# WS2811_Stepper.net
KiCad netlist of a schematic drawn in EAGLE
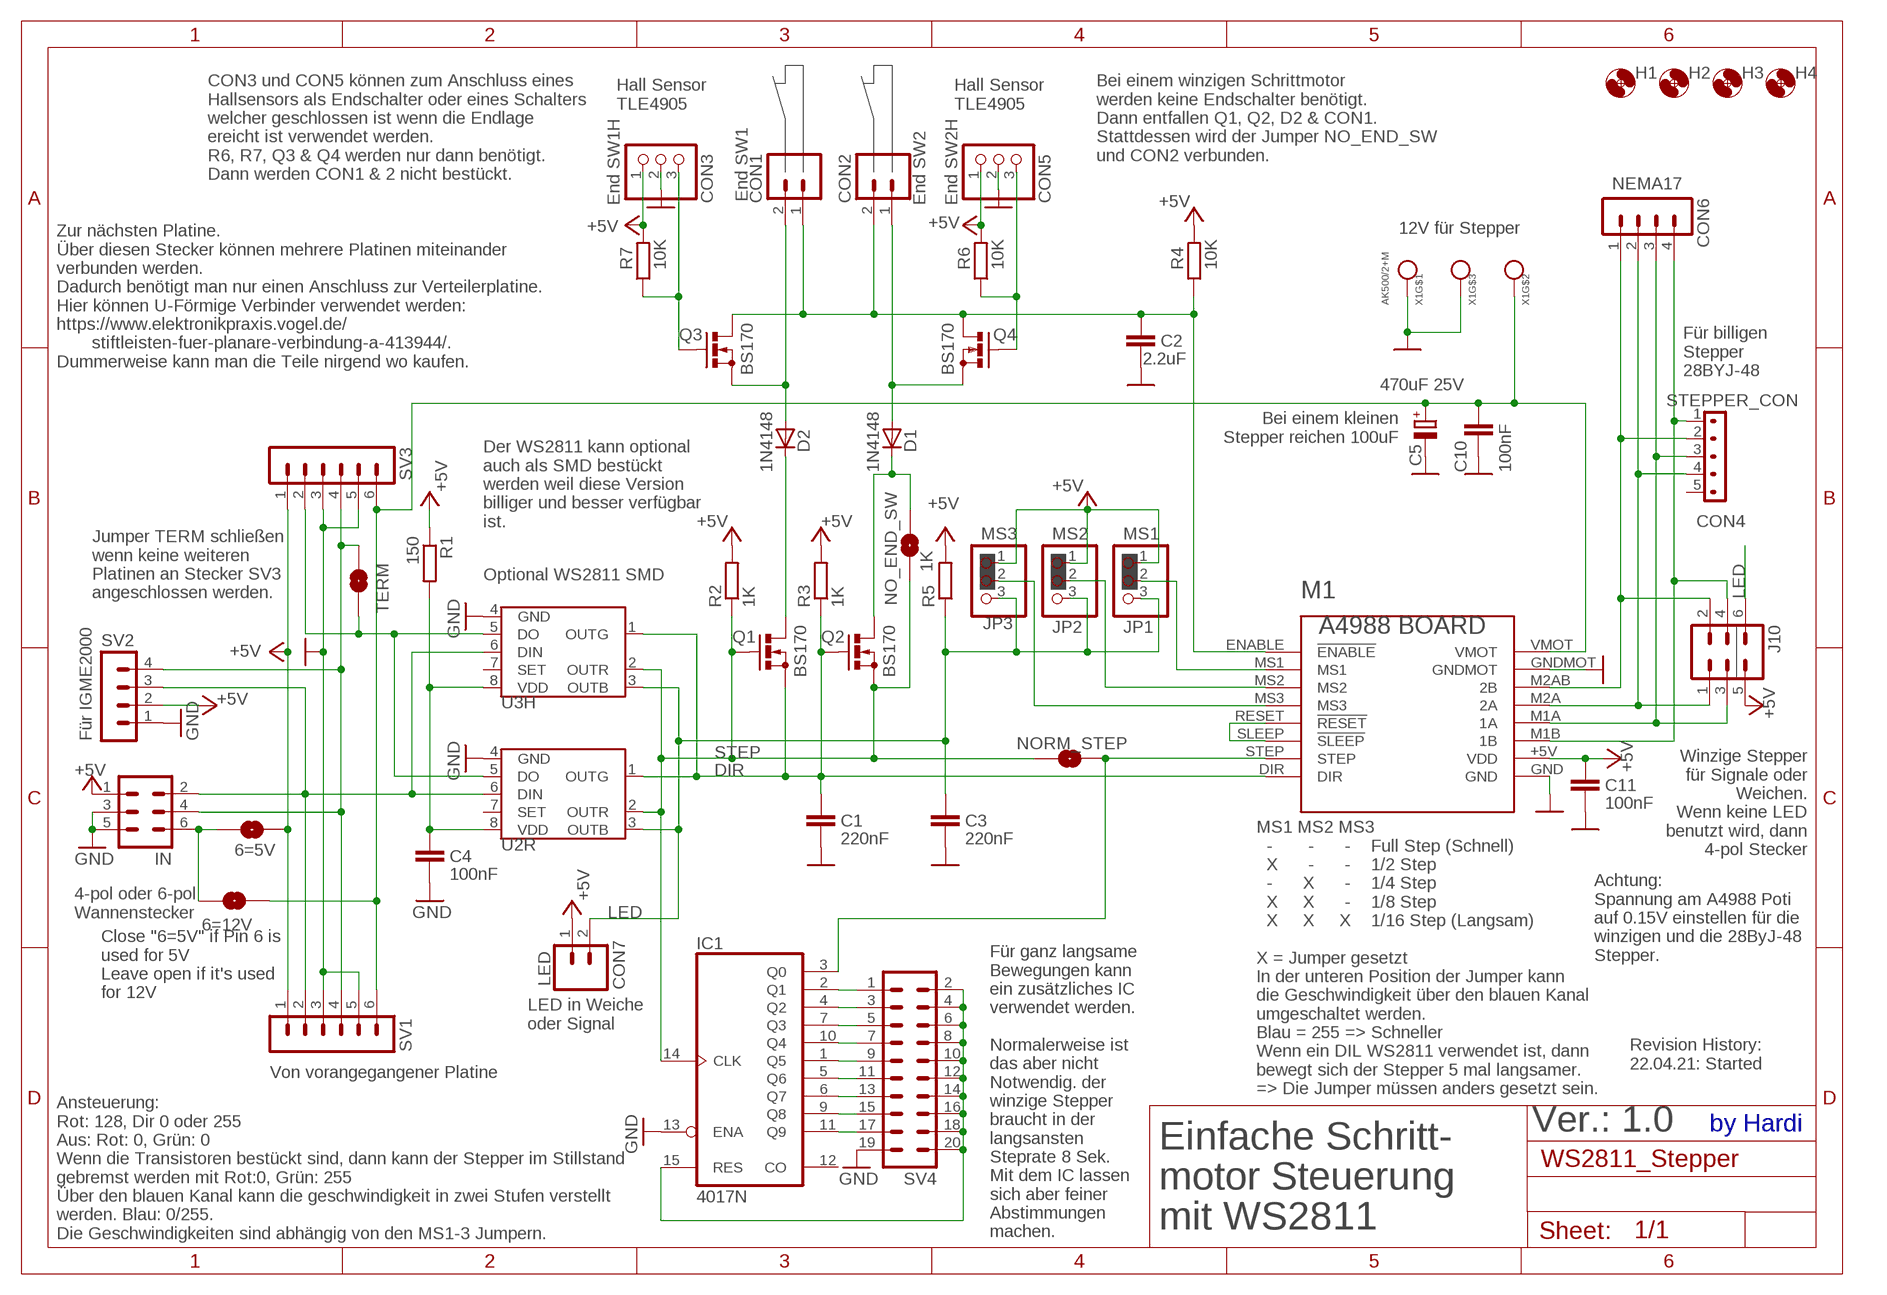
[diagram p0: schematic, sheet 1]

(export (version "E")
  (design (tool "Eeschema 10.0.6"))
  (components
    (comp (ref "6=5V")
      (value "SOLDERJUMPERNO")
      (footprint "eagle-import:SJ_2S-NO")
      (libsource (lib "eagle-import") (part "SOLDERJUMPERNO"))
    )
    (comp (ref "6=12V")
      (value "SOLDERJUMPERNO")
      (footprint "eagle-import:SJ_2S-NO")
      (libsource (lib "eagle-import") (part "SOLDERJUMPERNO"))
    )
    (comp (ref "C1")
      (value "220nF")
      (footprint "eagle-import:C050-024X044")
      (libsource (lib "eagle-import") (part "C-EU050-024X044"))
    )
    (comp (ref "C2")
      (value "2.2uF")
      (footprint "eagle-import:C050-024X044")
      (libsource (lib "eagle-import") (part "C-EU050-024X044"))
    )
    (comp (ref "C3")
      (value "220nF")
      (footprint "eagle-import:C050-024X044")
      (libsource (lib "eagle-import") (part "C-EU050-024X044"))
    )
    (comp (ref "C4")
      (value "100nF")
      (footprint "eagle-import:C050-024X044")
      (libsource (lib "eagle-import") (part "C-EU050-024X044"))
    )
    (comp (ref "C5")
      (value "470uF 25V")
      (footprint "eagle-import:E5-10,5")
      (libsource (lib "eagle-import") (part "CPOL-EUE5-10.5"))
    )
    (comp (ref "C10")
      (value "100nF")
      (footprint "eagle-import:C050-024X044")
      (libsource (lib "eagle-import") (part "C-EU050-024X044"))
    )
    (comp (ref "C11")
      (value "100nF")
      (footprint "eagle-import:C050-024X044")
      (libsource (lib "eagle-import") (part "C-EU050-024X044"))
    )
    (comp (ref "CON1")
      (value "End SW1")
      (footprint "eagle-import:1X02")
      (libsource (lib "eagle-import") (part "M02PTH"))
    )
    (comp (ref "CON2")
      (value "End SW2")
      (footprint "eagle-import:1X02")
      (libsource (lib "eagle-import") (part "M02PTH"))
    )
    (comp (ref "CON3")
      (value "End SW1H")
      (footprint "eagle-import:1X03-CLEANBIG")
      (libsource (lib "eagle-import") (part "PINHD-1X3CB"))
    )
    (comp (ref "CON4")
      (value "STEPPER_CON")
      (footprint "eagle-import:STEPPER_CON")
      (libsource (lib "eagle-import") (part "STEPPER_CON"))
    )
    (comp (ref "CON5")
      (value "End SW2H")
      (footprint "eagle-import:1X03-CLEANBIG")
      (libsource (lib "eagle-import") (part "PINHD-1X3CB"))
    )
    (comp (ref "CON6")
      (value "NEMA17")
      (footprint "eagle-import:MA04-1")
      (libsource (lib "eagle-import") (part "MA04-1"))
    )
    (comp (ref "CON7")
      (value "LED")
      (footprint "eagle-import:1X02")
      (libsource (lib "eagle-import") (part "M02PTH"))
    )
    (comp (ref "D1")
      (value "1N4148")
      (footprint "eagle-import:DO35-7")
      (libsource (lib "eagle-import") (part "1N4148DO35-7"))
    )
    (comp (ref "D2")
      (value "1N4148")
      (footprint "eagle-import:DO35-7")
      (libsource (lib "eagle-import") (part "1N4148DO35-7"))
    )
    (comp (ref "H1")
      (value "MOUNT-HOLE2.0")
      (footprint "eagle-import:2,0")
      (libsource (lib "eagle-import") (part "MOUNT-HOLE2.0"))
    )
    (comp (ref "H2")
      (value "MOUNT-HOLE2.0")
      (footprint "eagle-import:2,0")
      (libsource (lib "eagle-import") (part "MOUNT-HOLE2.0"))
    )
    (comp (ref "H3")
      (value "MOUNT-HOLE2.0")
      (footprint "eagle-import:2,0")
      (libsource (lib "eagle-import") (part "MOUNT-HOLE2.0"))
    )
    (comp (ref "H4")
      (value "MOUNT-HOLE2.0")
      (footprint "eagle-import:2,0")
      (libsource (lib "eagle-import") (part "MOUNT-HOLE2.0"))
    )
    (comp (ref "IC1")
      (value "4017N")
      (footprint "eagle-import:DIL16")
      (libsource (lib "eagle-import") (part "4017N"))
    )
    (comp (ref "IN")
      (value "ML6")
      (footprint "eagle-import:ML6")
      (libsource (lib "eagle-import") (part "ML6"))
    )
    (comp (ref "J10")
      (value "ML6")
      (footprint "eagle-import:ML6")
      (libsource (lib "eagle-import") (part "ML6"))
    )
    (comp (ref "JP1")
      (value "MS1")
      (footprint "eagle-import:1X03-CLEANBIG")
      (libsource (lib "eagle-import") (part "PINHD-1X3CB"))
    )
    (comp (ref "JP2")
      (value "MS2")
      (footprint "eagle-import:1X03-CLEANBIG")
      (libsource (lib "eagle-import") (part "PINHD-1X3CB"))
    )
    (comp (ref "JP3")
      (value "MS3")
      (footprint "eagle-import:1X03-CLEANBIG")
      (libsource (lib "eagle-import") (part "PINHD-1X3CB"))
    )
    (comp (ref "M1")
      (value "BOARD_A4988")
      (footprint "eagle-import:BOARD_A4988")
      (libsource (lib "eagle-import") (part "BOARD_A4988"))
    )
    (comp (ref "NORM_STEP")
      (value "SOLDERJUMPERNO")
      (footprint "eagle-import:SJ_2S-NO")
      (libsource (lib "eagle-import") (part "SOLDERJUMPERNO"))
    )
    (comp (ref "NO_END_SW")
      (value "SOLDERJUMPERNO")
      (footprint "eagle-import:SJ_2S-NO")
      (libsource (lib "eagle-import") (part "SOLDERJUMPERNO"))
    )
    (comp (ref "Q1")
      (value "BS170")
      (footprint "eagle-import:SOT54E")
      (libsource (lib "eagle-import") (part "BS170"))
    )
    (comp (ref "Q2")
      (value "BS170")
      (footprint "eagle-import:SOT54E")
      (libsource (lib "eagle-import") (part "BS170"))
    )
    (comp (ref "Q3")
      (value "BS170")
      (footprint "eagle-import:SOT54E")
      (libsource (lib "eagle-import") (part "BS170"))
    )
    (comp (ref "Q4")
      (value "BS170")
      (footprint "eagle-import:SOT54E")
      (libsource (lib "eagle-import") (part "BS170"))
    )
    (comp (ref "R1")
      (value "150")
      (footprint "eagle-import:RCL_0204_7")
      (libsource (lib "eagle-import") (part "RCL_R-EU_0204/7"))
    )
    (comp (ref "R2")
      (value "1K")
      (footprint "eagle-import:RCL_0204_7")
      (libsource (lib "eagle-import") (part "RCL_R-EU_0204/7"))
    )
    (comp (ref "R3")
      (value "1K")
      (footprint "eagle-import:RCL_0204_7")
      (libsource (lib "eagle-import") (part "RCL_R-EU_0204/7"))
    )
    (comp (ref "R4")
      (value "10K")
      (footprint "eagle-import:RCL_0204_7")
      (libsource (lib "eagle-import") (part "RCL_R-EU_0204/7"))
    )
    (comp (ref "R5")
      (value "1K")
      (footprint "eagle-import:RCL_0204_7")
      (libsource (lib "eagle-import") (part "RCL_R-EU_0204/7"))
    )
    (comp (ref "R6")
      (value "10K")
      (footprint "eagle-import:RCL_0204_7")
      (libsource (lib "eagle-import") (part "RCL_R-EU_0204/7"))
    )
    (comp (ref "R7")
      (value "10K")
      (footprint "eagle-import:RCL_0204_7")
      (libsource (lib "eagle-import") (part "RCL_R-EU_0204/7"))
    )
    (comp (ref "SV1")
      (value "MA06-1")
      (footprint "eagle-import:MA06-1")
      (libsource (lib "eagle-import") (part "MA06-1"))
    )
    (comp (ref "SV2")
      (value "MA04-1")
      (footprint "eagle-import:MA04-1")
      (libsource (lib "eagle-import") (part "MA04-1"))
    )
    (comp (ref "SV3")
      (value "MA06-1")
      (footprint "eagle-import:MA06-1")
      (libsource (lib "eagle-import") (part "MA06-1"))
    )
    (comp (ref "SV4")
      (value "MA10-2")
      (footprint "eagle-import:MA10-2")
      (libsource (lib "eagle-import") (part "MA10-2"))
    )
    (comp (ref "TERM")
      (value "SOLDERJUMPERNO")
      (footprint "eagle-import:SJ_2S-NO")
      (libsource (lib "eagle-import") (part "SOLDERJUMPERNO"))
    )
    (comp (ref "U2R")
      (value "WS2811")
      (footprint "eagle-import:S3PO_MODUL_WS2811_SOUND_MP3-TF-16P_WS2811_AND_ATTINY_WS2811_DIP08")
      (libsource (lib "eagle-import") (part "S3PO_MODUL_WS2811_SOUND_MP3-TF-16P_WS2811_AND_ATTINY_WS2811-ICTINY45-20-DIP"))
    )
    (comp (ref "U3H")
      (value "WS2811 SOT-8")
      (footprint "eagle-import:SOP8")
      (libsource (lib "eagle-import") (part "S3PO_MODUL_WS2811_SOUND_MP3-TF-16P_WS2811_AND_ATTINY_WS2811-ICSOP8"))
    )
    (comp (ref "X1")
      (value "AK500/2+M")
      (footprint "eagle-import:AK500_2+M")
      (libsource (lib "eagle-import") (part "AK500/2+M"))
    )
  )
  (nets
    (net (code "1") (name "+5V") (class "Default")
      (node (ref "6=5V") (pin "2") (pinfunction "2_2") (pintype "passive"))
      (node (ref "C11") (pin "1") (pinfunction "1_1") (pintype "passive"))
      (node (ref "CON3") (pin "1") (pinfunction "1_1") (pintype "passive"))
      (node (ref "CON5") (pin "1") (pinfunction "1_1") (pintype "passive"))
      (node (ref "CON7") (pin "1") (pinfunction "1_1") (pintype "passive"))
      (node (ref "IN") (pin "1") (pinfunction "1_1") (pintype "passive"))
      (node (ref "J10") (pin "5") (pinfunction "5_5") (pintype "passive"))
      (node (ref "JP1") (pin "1") (pinfunction "1_1") (pintype "passive"))
      (node (ref "JP2") (pin "1") (pinfunction "1_1") (pintype "passive"))
      (node (ref "JP3") (pin "1") (pinfunction "1_1") (pintype "passive"))
      (node (ref "M1") (pin "+5V") (pinfunction "VDD_+5V") (pintype "power_in"))
      (node (ref "R1") (pin "1") (pinfunction "1_1") (pintype "passive"))
      (node (ref "R2") (pin "2") (pinfunction "2_2") (pintype "passive"))
      (node (ref "R3") (pin "2") (pinfunction "2_2") (pintype "passive"))
      (node (ref "R4") (pin "2") (pinfunction "2_2") (pintype "passive"))
      (node (ref "R5") (pin "2") (pinfunction "2_2") (pintype "passive"))
      (node (ref "R6") (pin "2") (pinfunction "2_2") (pintype "passive"))
      (node (ref "R7") (pin "2") (pinfunction "2_2") (pintype "passive"))
      (node (ref "SV1") (pin "1") (pinfunction "1_1") (pintype "passive"))
      (node (ref "SV2") (pin "2") (pinfunction "2_2") (pintype "passive"))
      (node (ref "SV3") (pin "1") (pinfunction "1_1") (pintype "passive"))
    )
    (net (code "2") (name "/DIR") (class "Default")
      (node (ref "C1") (pin "1") (pinfunction "1_1") (pintype "passive"))
      (node (ref "M1") (pin "DIR") (pinfunction "DIR_DIR") (pintype "input"))
      (node (ref "Q1") (pin "S") (pinfunction "S_S") (pintype "passive"))
      (node (ref "Q2") (pin "G") (pinfunction "G_G") (pintype "passive"))
      (node (ref "R3") (pin "1") (pinfunction "1_1") (pintype "passive"))
      (node (ref "U2R") (pin "1") (pinfunction "OUTG_1") (pintype "open_collector"))
      (node (ref "U3H") (pin "1") (pinfunction "OUTG_1") (pintype "open_collector"))
    )
    (net (code "3") (name "/LED") (class "Default")
      (node (ref "C3") (pin "1") (pinfunction "1_1") (pintype "passive"))
      (node (ref "CON7") (pin "2") (pinfunction "2_2") (pintype "passive"))
      (node (ref "J10") (pin "6") (pinfunction "6_6") (pintype "passive"))
      (node (ref "JP1") (pin "3") (pinfunction "3_3") (pintype "passive"))
      (node (ref "JP2") (pin "3") (pinfunction "3_3") (pintype "passive"))
      (node (ref "JP3") (pin "3") (pinfunction "3_3") (pintype "passive"))
      (node (ref "R5") (pin "1") (pinfunction "1_1") (pintype "passive"))
      (node (ref "U2R") (pin "3") (pinfunction "OUTB_3") (pintype "open_collector"))
      (node (ref "U3H") (pin "3") (pinfunction "OUTB_3") (pintype "open_collector"))
    )
    (net (code "4") (name "/STEP") (class "Default")
      (node (ref "IC1") (pin "14") (pinfunction "CLK_14") (pintype "input"))
      (node (ref "NORM_STEP") (pin "1") (pinfunction "1_1") (pintype "passive"))
      (node (ref "NO_END_SW") (pin "2") (pinfunction "2_2") (pintype "passive"))
      (node (ref "Q1") (pin "G") (pinfunction "G_G") (pintype "passive"))
      (node (ref "Q2") (pin "S") (pinfunction "S_S") (pintype "passive"))
      (node (ref "R2") (pin "1") (pinfunction "1_1") (pintype "passive"))
      (node (ref "U2R") (pin "2") (pinfunction "OUTR_2") (pintype "open_collector"))
      (node (ref "U3H") (pin "2") (pinfunction "OUTR_2") (pintype "open_collector"))
    )
    (net (code "5") (name "GND") (class "Default")
      (node (ref "C1") (pin "2") (pinfunction "2_2") (pintype "passive"))
      (node (ref "C10") (pin "2") (pinfunction "2_2") (pintype "passive"))
      (node (ref "C11") (pin "2") (pinfunction "2_2") (pintype "passive"))
      (node (ref "C2") (pin "2") (pinfunction "2_2") (pintype "passive"))
      (node (ref "C3") (pin "2") (pinfunction "2_2") (pintype "passive"))
      (node (ref "C4") (pin "2") (pinfunction "2_2") (pintype "passive"))
      (node (ref "C5") (pin "-") (pinfunction "-_-") (pintype "passive"))
      (node (ref "CON3") (pin "2") (pinfunction "2_2") (pintype "passive"))
      (node (ref "CON5") (pin "2") (pinfunction "2_2") (pintype "passive"))
      (node (ref "IC1") (pin "13") (pinfunction "ENA_13") (pintype "input"))
      (node (ref "IN") (pin "3") (pinfunction "3_3") (pintype "passive"))
      (node (ref "IN") (pin "5") (pinfunction "5_5") (pintype "passive"))
      (node (ref "M1") (pin "GND") (pinfunction "GND_GND") (pintype "power_in"))
      (node (ref "M1") (pin "GNDMOT") (pinfunction "GNDMOT_GNDMOT") (pintype "power_in"))
      (node (ref "SV1") (pin "3") (pinfunction "3_3") (pintype "passive"))
      (node (ref "SV1") (pin "5") (pinfunction "5_5") (pintype "passive"))
      (node (ref "SV2") (pin "1") (pinfunction "1_1") (pintype "passive"))
      (node (ref "SV3") (pin "3") (pinfunction "3_3") (pintype "passive"))
      (node (ref "SV3") (pin "5") (pinfunction "5_5") (pintype "passive"))
      (node (ref "SV4") (pin "19") (pinfunction "19_19") (pintype "passive"))
      (node (ref "U2R") (pin "4") (pinfunction "GND_4") (pintype "power_in"))
      (node (ref "U3H") (pin "4") (pinfunction "GND_4") (pintype "power_in"))
      (node (ref "X1") (pin "1") (pinfunction "KL_1") (pintype "passive"))
      (node (ref "X1") (pin "M") (pinfunction "KL_M") (pintype "passive"))
    )
    (net (code "6") (name "Net-(6=12V-Pad2)") (class "Default")
      (node (ref "6=12V") (pin "2") (pinfunction "2_2") (pintype "passive"))
      (node (ref "6=5V") (pin "1") (pinfunction "1_1") (pintype "passive"))
      (node (ref "IN") (pin "6") (pinfunction "6_6") (pintype "passive"))
    )
    (net (code "7") (name "Net-(CON1-Pad2)") (class "Default")
      (node (ref "CON1") (pin "2") (pinfunction "2_2") (pintype "passive"))
      (node (ref "D2") (pin "A") (pinfunction "A_A") (pintype "passive"))
      (node (ref "Q3") (pin "S") (pinfunction "S_S") (pintype "passive"))
    )
    (net (code "8") (name "Net-(CON2-Pad1)") (class "Default")
      (node (ref "CON2") (pin "1") (pinfunction "1_1") (pintype "passive"))
      (node (ref "D1") (pin "A") (pinfunction "A_A") (pintype "passive"))
      (node (ref "Q4") (pin "S") (pinfunction "S_S") (pintype "passive"))
    )
    (net (code "9") (name "Net-(CON3-Pad3)") (class "Default")
      (node (ref "CON3") (pin "3") (pinfunction "3_3") (pintype "passive"))
      (node (ref "Q3") (pin "G") (pinfunction "G_G") (pintype "passive"))
      (node (ref "R7") (pin "1") (pinfunction "1_1") (pintype "passive"))
    )
    (net (code "10") (name "Net-(CON5-Pad3)") (class "Default")
      (node (ref "CON5") (pin "3") (pinfunction "3_3") (pintype "passive"))
      (node (ref "Q4") (pin "G") (pinfunction "G_G") (pintype "passive"))
      (node (ref "R6") (pin "1") (pinfunction "1_1") (pintype "passive"))
    )
    (net (code "11") (name "Net-(D1-PadC)") (class "Default")
      (node (ref "D1") (pin "C") (pinfunction "C_C") (pintype "passive"))
      (node (ref "NO_END_SW") (pin "1") (pinfunction "1_1") (pintype "passive"))
      (node (ref "Q2") (pin "D") (pinfunction "D_D") (pintype "passive"))
    )
    (net (code "12") (name "Net-(D2-PadC)") (class "Default")
      (node (ref "D2") (pin "C") (pinfunction "C_C") (pintype "passive"))
      (node (ref "Q1") (pin "D") (pinfunction "D_D") (pintype "passive"))
    )
    (net (code "13") (name "Net-(IC1A-Q0)") (class "Default")
      (node (ref "IC1") (pin "3") (pinfunction "Q0_3") (pintype "output"))
      (node (ref "M1") (pin "STEP") (pinfunction "STEP_STEP") (pintype "input"))
      (node (ref "NORM_STEP") (pin "2") (pinfunction "2_2") (pintype "passive"))
    )
    (net (code "14") (name "Net-(IC1A-Q1)") (class "Default")
      (node (ref "IC1") (pin "2") (pinfunction "Q1_2") (pintype "output"))
      (node (ref "SV4") (pin "1") (pinfunction "1_1") (pintype "passive"))
    )
    (net (code "15") (name "Net-(IC1A-Q2)") (class "Default")
      (node (ref "IC1") (pin "4") (pinfunction "Q2_4") (pintype "output"))
      (node (ref "SV4") (pin "3") (pinfunction "3_3") (pintype "passive"))
    )
    (net (code "16") (name "Net-(IC1A-Q3)") (class "Default")
      (node (ref "IC1") (pin "7") (pinfunction "Q3_7") (pintype "output"))
      (node (ref "SV4") (pin "5") (pinfunction "5_5") (pintype "passive"))
    )
    (net (code "17") (name "Net-(IC1A-Q4)") (class "Default")
      (node (ref "IC1") (pin "10") (pinfunction "Q4_10") (pintype "output"))
      (node (ref "SV4") (pin "7") (pinfunction "7_7") (pintype "passive"))
    )
    (net (code "18") (name "Net-(IC1A-Q5)") (class "Default")
      (node (ref "IC1") (pin "1") (pinfunction "Q5_1") (pintype "output"))
      (node (ref "SV4") (pin "9") (pinfunction "9_9") (pintype "passive"))
    )
    (net (code "19") (name "Net-(IC1A-Q6)") (class "Default")
      (node (ref "IC1") (pin "5") (pinfunction "Q6_5") (pintype "output"))
      (node (ref "SV4") (pin "11") (pinfunction "11_11") (pintype "passive"))
    )
    (net (code "20") (name "Net-(IC1A-Q7)") (class "Default")
      (node (ref "IC1") (pin "6") (pinfunction "Q7_6") (pintype "output"))
      (node (ref "SV4") (pin "13") (pinfunction "13_13") (pintype "passive"))
    )
    (net (code "21") (name "Net-(IC1A-Q8)") (class "Default")
      (node (ref "IC1") (pin "9") (pinfunction "Q8_9") (pintype "output"))
      (node (ref "SV4") (pin "15") (pinfunction "15_15") (pintype "passive"))
    )
    (net (code "22") (name "Net-(IC1A-Q9)") (class "Default")
      (node (ref "IC1") (pin "11") (pinfunction "Q9_11") (pintype "output"))
      (node (ref "SV4") (pin "17") (pinfunction "17_17") (pintype "passive"))
    )
    (net (code "23") (name "Net-(IC1A-RES)") (class "Default")
      (node (ref "IC1") (pin "15") (pinfunction "RES_15") (pintype "input"))
      (node (ref "SV4") (pin "10") (pinfunction "10_10") (pintype "passive"))
      (node (ref "SV4") (pin "12") (pinfunction "12_12") (pintype "passive"))
      (node (ref "SV4") (pin "14") (pinfunction "14_14") (pintype "passive"))
      (node (ref "SV4") (pin "16") (pinfunction "16_16") (pintype "passive"))
      (node (ref "SV4") (pin "18") (pinfunction "18_18") (pintype "passive"))
      (node (ref "SV4") (pin "2") (pinfunction "2_2") (pintype "passive"))
      (node (ref "SV4") (pin "20") (pinfunction "20_20") (pintype "passive"))
      (node (ref "SV4") (pin "4") (pinfunction "4_4") (pintype "passive"))
      (node (ref "SV4") (pin "6") (pinfunction "6_6") (pintype "passive"))
      (node (ref "SV4") (pin "8") (pinfunction "8_8") (pintype "passive"))
    )
    (net (code "24") (name "Net-(IN-Pad4)") (class "Default")
      (node (ref "IN") (pin "4") (pinfunction "4_4") (pintype "passive"))
      (node (ref "SV1") (pin "4") (pinfunction "4_4") (pintype "passive"))
      (node (ref "SV2") (pin "4") (pinfunction "4_4") (pintype "passive"))
      (node (ref "SV3") (pin "4") (pinfunction "4_4") (pintype "passive"))
      (node (ref "TERM") (pin "1") (pinfunction "1_1") (pintype "passive"))
    )
    (net (code "25") (name "Net-(JP1-Pad2)") (class "Default")
      (node (ref "JP1") (pin "2") (pinfunction "2_2") (pintype "passive"))
      (node (ref "M1") (pin "MS1") (pinfunction "MS1_MS1") (pintype "input"))
    )
    (net (code "26") (name "Net-(JP2-Pad2)") (class "Default")
      (node (ref "JP2") (pin "2") (pinfunction "2_2") (pintype "passive"))
      (node (ref "M1") (pin "MS2") (pinfunction "MS2_MS2") (pintype "input"))
    )
    (net (code "27") (name "Net-(JP3-Pad2)") (class "Default")
      (node (ref "JP3") (pin "2") (pinfunction "2_2") (pintype "passive"))
      (node (ref "M1") (pin "MS3") (pinfunction "MS3_MS3") (pintype "input"))
    )
    (net (code "28") (name "Net-(M1-1A)") (class "Default")
      (node (ref "CON4") (pin "3") (pinfunction "3_3") (pintype "passive"))
      (node (ref "CON6") (pin "3") (pinfunction "3_3") (pintype "passive"))
      (node (ref "J10") (pin "3") (pinfunction "3_3") (pintype "passive"))
      (node (ref "M1") (pin "M1A") (pinfunction "1A_M1A") (pintype "output"))
    )
    (net (code "29") (name "Net-(M1-1B)") (class "Default")
      (node (ref "CON4") (pin "1") (pinfunction "1_1") (pintype "passive"))
      (node (ref "CON6") (pin "4") (pinfunction "4_4") (pintype "passive"))
      (node (ref "J10") (pin "4") (pinfunction "4_4") (pintype "passive"))
      (node (ref "M1") (pin "M1B") (pinfunction "1B_M1B") (pintype "output"))
    )
    (net (code "30") (name "Net-(M1-2A)") (class "Default")
      (node (ref "CON4") (pin "4") (pinfunction "4_4") (pintype "passive"))
      (node (ref "CON6") (pin "2") (pinfunction "2_2") (pintype "passive"))
      (node (ref "J10") (pin "1") (pinfunction "1_1") (pintype "passive"))
      (node (ref "M1") (pin "M2A") (pinfunction "2A_M2A") (pintype "output"))
    )
    (net (code "31") (name "Net-(M1-2B)") (class "Default")
      (node (ref "CON4") (pin "2") (pinfunction "2_2") (pintype "passive"))
      (node (ref "CON6") (pin "1") (pinfunction "1_1") (pintype "passive"))
      (node (ref "J10") (pin "2") (pinfunction "2_2") (pintype "passive"))
      (node (ref "M1") (pin "M2AB") (pinfunction "2B_M2AB") (pintype "output"))
    )
    (net (code "32") (name "Net-(M1-~{ENABLE})") (class "Default")
      (node (ref "C2") (pin "1") (pinfunction "1_1") (pintype "passive"))
      (node (ref "CON1") (pin "1") (pinfunction "1_1") (pintype "passive"))
      (node (ref "CON2") (pin "2") (pinfunction "2_2") (pintype "passive"))
      (node (ref "M1") (pin "ENABLE") (pinfunction "~{ENABLE}_ENABLE") (pintype "input"))
      (node (ref "Q3") (pin "D") (pinfunction "D_D") (pintype "passive"))
      (node (ref "Q4") (pin "D") (pinfunction "D_D") (pintype "passive"))
      (node (ref "R4") (pin "1") (pinfunction "1_1") (pintype "passive"))
    )
    (net (code "33") (name "Net-(M1-~{RESET})") (class "Default")
      (node (ref "M1") (pin "RESET") (pinfunction "~{RESET}_RESET") (pintype "input"))
      (node (ref "M1") (pin "SLEEP") (pinfunction "~{SLEEP}_SLEEP") (pintype "input"))
    )
    (net (code "34") (name "Net-(U2R-DIN)") (class "Default")
      (node (ref "IN") (pin "2") (pinfunction "2_2") (pintype "passive"))
      (node (ref "SV1") (pin "2") (pinfunction "2_2") (pintype "passive"))
      (node (ref "SV2") (pin "3") (pinfunction "3_3") (pintype "passive"))
      (node (ref "U2R") (pin "6") (pinfunction "DIN_6") (pintype "input"))
      (node (ref "U3H") (pin "6") (pinfunction "DIN_6") (pintype "input"))
    )
    (net (code "35") (name "Net-(U2R-DO)") (class "Default")
      (node (ref "SV3") (pin "2") (pinfunction "2_2") (pintype "passive"))
      (node (ref "TERM") (pin "2") (pinfunction "2_2") (pintype "passive"))
      (node (ref "U2R") (pin "5") (pinfunction "DO_5") (pintype "output"))
      (node (ref "U3H") (pin "5") (pinfunction "DO_5") (pintype "output"))
    )
    (net (code "36") (name "Net-(U2R-VDD)") (class "Default")
      (node (ref "C4") (pin "1") (pinfunction "1_1") (pintype "passive"))
      (node (ref "R1") (pin "2") (pinfunction "2_2") (pintype "passive"))
      (node (ref "U2R") (pin "8") (pinfunction "VDD_8") (pintype "power_in"))
      (node (ref "U3H") (pin "8") (pinfunction "VDD_8") (pintype "power_in"))
    )
    (net (code "37") (name "Net-(X1B-KL)") (class "Default")
      (node (ref "6=12V") (pin "1") (pinfunction "1_1") (pintype "passive"))
      (node (ref "C10") (pin "1") (pinfunction "1_1") (pintype "passive"))
      (node (ref "C5") (pin "+") (pinfunction "+_+") (pintype "passive"))
      (node (ref "M1") (pin "VMOT") (pinfunction "VMOT_VMOT") (pintype "power_in"))
      (node (ref "SV1") (pin "6") (pinfunction "6_6") (pintype "passive"))
      (node (ref "SV3") (pin "6") (pinfunction "6_6") (pintype "passive"))
      (node (ref "X1") (pin "2") (pinfunction "KL_2") (pintype "passive"))
    )
    (net (code "38") (name "unconnected-(CON4-Pad5)") (class "Default")
      (node (ref "CON4") (pin "5") (pinfunction "5_5") (pintype "passive"))
    )
    (net (code "39") (name "unconnected-(IC1A-CO-Pad12)") (class "Default")
      (node (ref "IC1") (pin "12") (pinfunction "CO_12") (pintype "output"))
    )
    (net (code "40") (name "unconnected-(U2R-SET-Pad7)") (class "Default")
      (node (ref "U2R") (pin "7") (pinfunction "SET_7") (pintype "bidirectional"))
    )
    (net (code "41") (name "unconnected-(U3H-SET-Pad7)") (class "Default")
      (node (ref "U3H") (pin "7") (pinfunction "SET_7") (pintype "bidirectional"))
    )
  )
)
